# LM317.net
KiCad netlist of a schematic drawn in Altium Designer
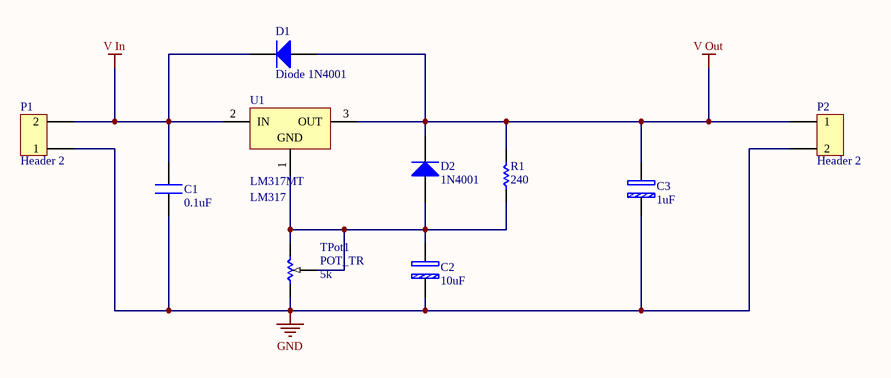
[diagram p0: LM317.SchDoc]

(export (version "E")
  (design (tool "Eeschema 10.0.6"))
  (components
    (comp (ref "C1")
      (value "0.1uF")
      (footprint "Capacitor")
      (fields (field (name "Comment") "CapN03"))
      (libsource (lib "Composants_Projet_Sheet_TP9") (part "CapN"))
    )
    (comp (ref "C2")
      (value "10uF")
      (footprint "Capacitor_Ch")
      (fields (field (name "Comment") "CapCh10u"))
      (libsource (lib "Composants_Projet_Sheet_TP9") (part "CapChN"))
    )
    (comp (ref "C3")
      (value "1uF")
      (footprint "Capacitor_Ch")
      (fields (field (name "Comment") "CapCh10u"))
      (libsource (lib "Composants_Projet_Sheet_TP9") (part "CapChN"))
    )
    (comp (ref "D1")
      (value "Diode 1N4001")
      (footprint "DO-41")
      (description "1 Amp General Purpose Rectifier")
      (fields (field (name "PUBLISHER") "Altium Limited"))
      (libsource (lib "Miscellaneous Devices") (part "Diode 1N4001"))
    )
    (comp (ref "D2")
      (value "1N4001")
      (footprint "DO-41")
      (description "1 Amp General Purpose Rectifier")
      (fields (field (name "PUBLISHER") "Altium Limited"))
      (libsource (lib "Miscellaneous Devices") (part "Diode 1N4001"))
    )
    (comp (ref "P1")
      (value "Header 2")
      (footprint "CONNECTOR-B2")
      (description "Header 2 pins")
      (libsource (lib "") (part "Block_Conn_1"))
    )
    (comp (ref "P2")
      (value "Header 2")
      (footprint "CONNECTOR-B2")
      (description "Header 2 pins")
      (libsource (lib "Composants_Projet_Sheet_TP9") (part "Block_Conn"))
    )
    (comp (ref "R1")
      (value "240")
      (footprint "Res10mm")
      (fields (field (name "Comment") "Res_010"))
      (libsource (lib "Composants_Projet_Sheet_TP9") (part "Res_010"))
    )
    (comp (ref "TPot1")
      (value "POT_TR")
      (footprint "POTENTIOMETER_N_Trimmer")
      (fields (field (name "ALTIUM_VALUE") "5k"))
      (libsource (lib "Composants_Projet_Sheet_TP9") (part "POT_TR"))
    )
    (comp (ref "U1")
      (value "LM317MT")
      (footprint "TO220V")
      (description "Regulator Voltage")
      (fields (field (name "FOOOTPRINT") "LM317"))
      (libsource (lib "Composants_Projet_Sheet_TP9") (part "LM317MT"))
    )
  )
  (nets
    (net (code "1") (name "GND") (class "Default")
      (node (ref "C1") (pin "1") (pinfunction "1_1") (pintype "passive"))
      (node (ref "C2") (pin "2") (pinfunction "2_2") (pintype "passive"))
      (node (ref "C3") (pin "2") (pinfunction "2_2") (pintype "passive"))
      (node (ref "P1") (pin "1") (pinfunction "1_1") (pintype "power_in"))
      (node (ref "P2") (pin "2") (pinfunction "2_2") (pintype "power_in"))
      (node (ref "TPot1") (pin "1") (pinfunction "1_1") (pintype "passive"))
    )
    (net (code "2") (name "Net-(D2-A)") (class "Default")
      (node (ref "C2") (pin "1") (pinfunction "1_1") (pintype "passive"))
      (node (ref "D2") (pin "1") (pinfunction "A_1") (pintype "passive"))
      (node (ref "R1") (pin "1") (pinfunction "1_1") (pintype "passive"))
      (node (ref "TPot1") (pin "2") (pinfunction "2_2") (pintype "input"))
      (node (ref "TPot1") (pin "3") (pinfunction "3_3") (pintype "passive"))
      (node (ref "U1") (pin "1") (pinfunction "ADJ_1") (pintype "passive"))
    )
    (net (code "3") (name "V In") (class "Default")
      (node (ref "C1") (pin "2") (pinfunction "2_2") (pintype "passive"))
      (node (ref "D1") (pin "2") (pinfunction "K_2") (pintype "passive"))
      (node (ref "P1") (pin "2") (pinfunction "2_2") (pintype "power_in"))
      (node (ref "U1") (pin "2") (pinfunction "IN_2") (pintype "passive"))
    )
    (net (code "4") (name "V Out") (class "Default")
      (node (ref "C3") (pin "1") (pinfunction "1_1") (pintype "passive"))
      (node (ref "D1") (pin "1") (pinfunction "A_1") (pintype "passive"))
      (node (ref "D2") (pin "2") (pinfunction "K_2") (pintype "passive"))
      (node (ref "P2") (pin "1") (pinfunction "1_1") (pintype "power_in"))
      (node (ref "R1") (pin "2") (pinfunction "2_2") (pintype "passive"))
      (node (ref "U1") (pin "3") (pinfunction "OUT_3") (pintype "passive"))
    )
  )
)
